# Microcontroller.net
KiCad netlist of a schematic drawn in Altium Designer
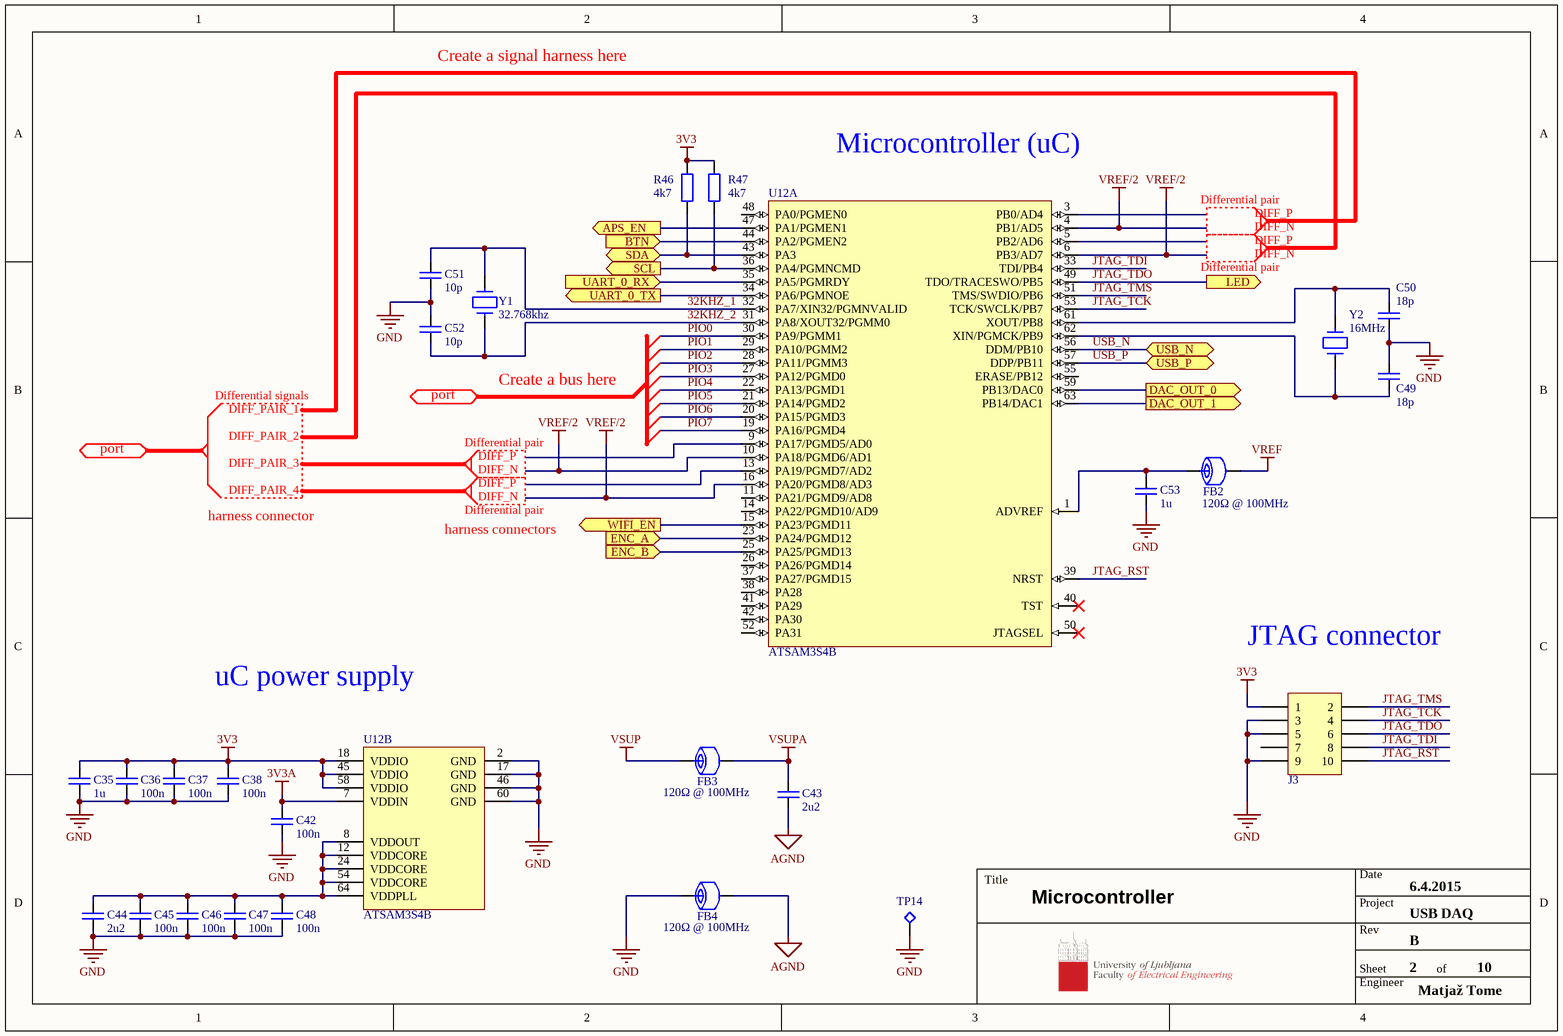
[diagram p0: Microcontroller.SchDoc]

(export (version "E")
  (design (tool "Eeschema 10.0.6"))
  (components
    (comp (ref "C35")
      (value "1u")
      (footprint "C_0603")
      (description "Generic capacitor")
      (fields (field (name "Comment") "comment"))
      (libsource (lib "DAQ") (part "Capacitor"))
    )
    (comp (ref "C36")
      (value "100n")
      (footprint "C_0603")
      (description "Generic capacitor")
      (fields (field (name "Comment") "comment"))
      (libsource (lib "DAQ") (part "Capacitor"))
    )
    (comp (ref "C37")
      (value "100n")
      (footprint "C_0603")
      (description "Generic capacitor")
      (fields (field (name "Comment") "comment"))
      (libsource (lib "DAQ") (part "Capacitor"))
    )
    (comp (ref "C38")
      (value "100n")
      (footprint "C_0603")
      (description "Generic capacitor")
      (fields (field (name "Comment") "comment"))
      (libsource (lib "DAQ") (part "Capacitor"))
    )
    (comp (ref "C42")
      (value "100n")
      (footprint "C_0603")
      (description "Generic capacitor")
      (fields (field (name "Comment") "comment"))
      (libsource (lib "DAQ") (part "Capacitor"))
    )
    (comp (ref "C43")
      (value "2u2")
      (footprint "C_0603")
      (description "Generic capacitor")
      (fields (field (name "Comment") "comment"))
      (libsource (lib "DAQ") (part "Capacitor"))
    )
    (comp (ref "C44")
      (value "2u2")
      (footprint "C_0603")
      (description "Generic capacitor")
      (fields (field (name "Comment") "comment"))
      (libsource (lib "DAQ") (part "Capacitor"))
    )
    (comp (ref "C45")
      (value "100n")
      (footprint "C_0603")
      (description "Generic capacitor")
      (fields (field (name "Comment") "comment"))
      (libsource (lib "DAQ") (part "Capacitor"))
    )
    (comp (ref "C46")
      (value "100n")
      (footprint "C_0603")
      (description "Generic capacitor")
      (fields (field (name "Comment") "comment"))
      (libsource (lib "DAQ") (part "Capacitor"))
    )
    (comp (ref "C47")
      (value "100n")
      (footprint "C_0603")
      (description "Generic capacitor")
      (fields (field (name "Comment") "comment"))
      (libsource (lib "DAQ") (part "Capacitor"))
    )
    (comp (ref "C48")
      (value "100n")
      (footprint "C_0603")
      (description "Generic capacitor")
      (fields (field (name "Comment") "comment"))
      (libsource (lib "DAQ") (part "Capacitor"))
    )
    (comp (ref "C49")
      (value "18p")
      (footprint "C_0603")
      (description "Generic capacitor")
      (fields (field (name "Comment") "comment"))
      (libsource (lib "DAQ") (part "Capacitor"))
    )
    (comp (ref "C50")
      (value "18p")
      (footprint "C_0603")
      (description "Generic capacitor")
      (fields (field (name "Comment") "comment"))
      (libsource (lib "DAQ") (part "Capacitor"))
    )
    (comp (ref "C51")
      (value "10p")
      (footprint "C_0603")
      (description "Generic capacitor")
      (fields (field (name "Comment") "comment"))
      (libsource (lib "DAQ") (part "Capacitor"))
    )
    (comp (ref "C52")
      (value "10p")
      (footprint "C_0603")
      (description "Generic capacitor")
      (fields (field (name "Comment") "comment"))
      (libsource (lib "DAQ") (part "Capacitor"))
    )
    (comp (ref "C53")
      (value "1u")
      (footprint "C_0603")
      (description "Generic capacitor")
      (fields (field (name "Comment") "comment"))
      (libsource (lib "DAQ") (part "Capacitor"))
    )
    (comp (ref "FB2")
      (value "120Ω @ 100MHz")
      (footprint "SMD_0805")
      (description "Ferrite Bead, 0805 [2012 Metric], 120 ohm, 800 mA, BLM21A Series, 0.15 ohm, ± 25%")
      (fields (field (name "MANUFACTURER") "Murata"))
      (libsource (lib "DAQ") (part "BLM21AG121SN1D"))
    )
    (comp (ref "FB3")
      (value "120Ω @ 100MHz")
      (footprint "SMD_0805")
      (description "Ferrite Bead, 0805 [2012 Metric], 120 ohm, 800 mA, BLM21A Series, 0.15 ohm, ± 25%")
      (fields (field (name "MANUFACTURER") "Murata"))
      (libsource (lib "DAQ") (part "BLM21AG121SN1D"))
    )
    (comp (ref "FB4")
      (value "120Ω @ 100MHz")
      (footprint "SMD_0805")
      (description "Ferrite Bead, 0805 [2012 Metric], 120 ohm, 800 mA, BLM21A Series, 0.15 ohm, ± 25%")
      (fields (field (name "MANUFACTURER") "Murata"))
      (libsource (lib "DAQ") (part "BLM21AG121SN1D"))
    )
    (comp (ref "J3")
      (value "M50-3600542")
      (footprint "HEADER_2X05_1.27mm")
      (description "Pin Header, Board-to-Board, 1.27 mm, 2 Rows, 10 Contacts, Surface Mount, Archer M50 Series")
      (fields (field (name "MANUFACTURER") "Harwin"))
      (libsource (lib "DAQ") (part "M50-3600542"))
    )
    (comp (ref "R46")
      (value "4k7")
      (footprint "R_0603")
      (description "Generic resistor")
      (fields (field (name "Comment") "comment"))
      (libsource (lib "DAQ") (part "Resistor"))
    )
    (comp (ref "R47")
      (value "4k7")
      (footprint "R_0603")
      (description "Generic resistor")
      (fields (field (name "Comment") "comment"))
      (libsource (lib "DAQ") (part "Resistor"))
    )
    (comp (ref "TP14")
      (value "testpoint")
      (footprint "TP1_FULL")
      (description "testpoint 1.5mm diameter no hole")
      (fields (field (name "PART NUMBER") "XXC0006"))
      (libsource (lib "DAQ") (part "Test Point"))
    )
    (comp (ref "U12")
      (value "ATSAM3S4B")
      (footprint "LQFP64")
      (description "Cortex M3 ARM microcontroller")
      (fields (field (name "PART NUMBER") "XAM0003") (field (name "MANUFACTURER") "Atmel"))
      (libsource (lib "DAQ") (part "ATSAM3SXB"))
    )
    (comp (ref "Y1")
      (value "32.768khz")
      (footprint "2X6_FLAT")
      (description "Crystal, 32.768 kHz, Cylinder Radial, 6.2mm x 2mm Dia, 12.5 pF, 20 ppm, R26 Series")
      (fields (field (name "PART NUMBER") "XCR0010") (field (name "MANUFACTURER") "RALTRON"))
      (libsource (lib "DAQ") (part "R26-32.768- 12.5"))
    )
    (comp (ref "Y2")
      (value "16MHz")
      (footprint "5X3.2")
      (description "Crystal, 16 MHz, SMD, 5mm x 3.2mm, 30 ppm, 18 pF, 30 ppm, 7A Series")
      (fields (field (name "MANUFACTURER") "TCX"))
      (libsource (lib "DAQ") (part "7A-16.000MAAJ-T"))
    )
  )
  (nets
    (net (code "1") (name "/32KHZ_1") (class "Default")
      (node (ref "C51") (pin "1") (pinfunction "1_1") (pintype "passive"))
      (node (ref "U12") (pin "32") (pinfunction "PA7/XIN32/PGMNVALID_32") (pintype "bidirectional"))
      (node (ref "Y1") (pin "2") (pinfunction "2_2") (pintype "passive"))
    )
    (net (code "2") (name "/32KHZ_2") (class "Default")
      (node (ref "C52") (pin "1") (pinfunction "1_1") (pintype "passive"))
      (node (ref "U12") (pin "31") (pinfunction "PA8/XOUT32/PGMM0_31") (pintype "bidirectional"))
      (node (ref "Y1") (pin "1") (pinfunction "1_1") (pintype "passive"))
    )
    (net (code "3") (name "/APS_EN") (class "Default")
      (node (ref "U12") (pin "47") (pinfunction "PA1/PGMEN1_47") (pintype "bidirectional"))
    )
    (net (code "4") (name "/BTN") (class "Default")
      (node (ref "U12") (pin "44") (pinfunction "PA2/PGMEN2_44") (pintype "bidirectional"))
    )
    (net (code "5") (name "/DAC_OUT_0") (class "Default")
      (node (ref "U12") (pin "59") (pinfunction "PB13/DAC0_59") (pintype "bidirectional"))
    )
    (net (code "6") (name "/DAC_OUT_1") (class "Default")
      (node (ref "U12") (pin "63") (pinfunction "PB14/DAC1_63") (pintype "bidirectional"))
    )
    (net (code "7") (name "/ENC_A") (class "Default")
      (node (ref "U12") (pin "23") (pinfunction "PA24/PGMD12_23") (pintype "bidirectional"))
    )
    (net (code "8") (name "/ENC_B") (class "Default")
      (node (ref "U12") (pin "25") (pinfunction "PA25/PGMD13_25") (pintype "bidirectional"))
    )
    (net (code "9") (name "/JTAG_RST") (class "Default")
      (node (ref "J3") (pin "10") (pinfunction "10_10") (pintype "passive"))
      (node (ref "U12") (pin "39") (pinfunction "NRST_39") (pintype "bidirectional"))
    )
    (net (code "10") (name "/JTAG_TCK") (class "Default")
      (node (ref "J3") (pin "4") (pinfunction "4_4") (pintype "passive"))
      (node (ref "U12") (pin "53") (pinfunction "TCK/SWCLK/PB7_53") (pintype "bidirectional"))
    )
    (net (code "11") (name "/JTAG_TDI") (class "Default")
      (node (ref "J3") (pin "8") (pinfunction "8_8") (pintype "passive"))
      (node (ref "U12") (pin "33") (pinfunction "TDI/PB4_33") (pintype "bidirectional"))
    )
    (net (code "12") (name "/JTAG_TDO") (class "Default")
      (node (ref "J3") (pin "6") (pinfunction "6_6") (pintype "passive"))
      (node (ref "U12") (pin "49") (pinfunction "TDO/TRACESWO/PB5_49") (pintype "bidirectional"))
    )
    (net (code "13") (name "/JTAG_TMS") (class "Default")
      (node (ref "J3") (pin "2") (pinfunction "2_2") (pintype "passive"))
      (node (ref "U12") (pin "51") (pinfunction "TMS/SWDIO/PB6_51") (pintype "bidirectional"))
    )
    (net (code "14") (name "/PIO0") (class "Default")
      (node (ref "U12") (pin "30") (pinfunction "PA9/PGMM1_30") (pintype "bidirectional"))
    )
    (net (code "15") (name "/PIO1") (class "Default")
      (node (ref "U12") (pin "29") (pinfunction "PA10/PGMM2_29") (pintype "bidirectional"))
    )
    (net (code "16") (name "/PIO2") (class "Default")
      (node (ref "U12") (pin "28") (pinfunction "PA11/PGMM3_28") (pintype "bidirectional"))
    )
    (net (code "17") (name "/PIO3") (class "Default")
      (node (ref "U12") (pin "27") (pinfunction "PA12/PGMD0_27") (pintype "bidirectional"))
    )
    (net (code "18") (name "/PIO4") (class "Default")
      (node (ref "U12") (pin "22") (pinfunction "PA13/PGMD1_22") (pintype "bidirectional"))
    )
    (net (code "19") (name "/PIO5") (class "Default")
      (node (ref "U12") (pin "21") (pinfunction "PA14/PGMD2_21") (pintype "bidirectional"))
    )
    (net (code "20") (name "/PIO6") (class "Default")
      (node (ref "U12") (pin "20") (pinfunction "PA15/PGMD3_20") (pintype "bidirectional"))
    )
    (net (code "21") (name "/PIO7") (class "Default")
      (node (ref "U12") (pin "19") (pinfunction "PA16/PGMD4_19") (pintype "bidirectional"))
    )
    (net (code "22") (name "/SCL") (class "Default")
      (node (ref "R47") (pin "1") (pintype "passive"))
      (node (ref "U12") (pin "36") (pinfunction "PA4/PGMNCMD_36") (pintype "bidirectional"))
    )
    (net (code "23") (name "/SDA") (class "Default")
      (node (ref "R46") (pin "1") (pintype "passive"))
      (node (ref "U12") (pin "43") (pinfunction "PA3_43") (pintype "bidirectional"))
    )
    (net (code "24") (name "/UART_0_RX") (class "Default")
      (node (ref "U12") (pin "35") (pinfunction "PA5/PGMRDY_35") (pintype "bidirectional"))
    )
    (net (code "25") (name "/UART_0_TX") (class "Default")
      (node (ref "U12") (pin "34") (pinfunction "PA6/PGMNOE_34") (pintype "bidirectional"))
    )
    (net (code "26") (name "/USB_N") (class "Default")
      (node (ref "U12") (pin "56") (pinfunction "DDM/PB10_56") (pintype "bidirectional"))
    )
    (net (code "27") (name "/USB_P") (class "Default")
      (node (ref "U12") (pin "57") (pinfunction "DDP/PB11_57") (pintype "bidirectional"))
    )
    (net (code "28") (name "/WIFI_EN") (class "Default")
      (node (ref "U12") (pin "15") (pinfunction "PA23/PGMD11_15") (pintype "bidirectional"))
    )
    (net (code "29") (name "3V3") (class "Default")
      (node (ref "C35") (pin "1") (pinfunction "1_1") (pintype "passive"))
      (node (ref "C36") (pin "1") (pinfunction "1_1") (pintype "passive"))
      (node (ref "C37") (pin "1") (pinfunction "1_1") (pintype "passive"))
      (node (ref "C38") (pin "1") (pinfunction "1_1") (pintype "passive"))
      (node (ref "J3") (pin "1") (pinfunction "1_1") (pintype "passive"))
      (node (ref "R46") (pin "2") (pintype "passive"))
      (node (ref "R47") (pin "2") (pintype "passive"))
      (node (ref "U12") (pin "18") (pinfunction "VDDIO_18") (pintype "power_in"))
      (node (ref "U12") (pin "45") (pinfunction "VDDIO_45") (pintype "power_in"))
      (node (ref "U12") (pin "58") (pinfunction "VDDIO_58") (pintype "power_in"))
    )
    (net (code "30") (name "3V3A") (class "Default")
      (node (ref "C42") (pin "1") (pinfunction "1_1") (pintype "passive"))
      (node (ref "U12") (pin "7") (pinfunction "VDDIN_7") (pintype "power_in"))
    )
    (net (code "31") (name "AGND") (class "Default")
      (node (ref "C43") (pin "2") (pinfunction "2_2") (pintype "passive"))
      (node (ref "FB4") (pin "2") (pintype "passive"))
    )
    (net (code "32") (name "GND") (class "Default")
      (node (ref "C35") (pin "2") (pinfunction "2_2") (pintype "passive"))
      (node (ref "C36") (pin "2") (pinfunction "2_2") (pintype "passive"))
      (node (ref "C37") (pin "2") (pinfunction "2_2") (pintype "passive"))
      (node (ref "C38") (pin "2") (pinfunction "2_2") (pintype "passive"))
      (node (ref "C42") (pin "2") (pinfunction "2_2") (pintype "passive"))
      (node (ref "C44") (pin "2") (pinfunction "2_2") (pintype "passive"))
      (node (ref "C45") (pin "2") (pinfunction "2_2") (pintype "passive"))
      (node (ref "C46") (pin "2") (pinfunction "2_2") (pintype "passive"))
      (node (ref "C47") (pin "2") (pinfunction "2_2") (pintype "passive"))
      (node (ref "C48") (pin "2") (pinfunction "2_2") (pintype "passive"))
      (node (ref "C49") (pin "2") (pinfunction "2_2") (pintype "passive"))
      (node (ref "C50") (pin "2") (pinfunction "2_2") (pintype "passive"))
      (node (ref "C51") (pin "2") (pinfunction "2_2") (pintype "passive"))
      (node (ref "C52") (pin "2") (pinfunction "2_2") (pintype "passive"))
      (node (ref "C53") (pin "2") (pinfunction "2_2") (pintype "passive"))
      (node (ref "FB4") (pin "1") (pintype "passive"))
      (node (ref "J3") (pin "3") (pinfunction "3_3") (pintype "passive"))
      (node (ref "J3") (pin "5") (pinfunction "5_5") (pintype "passive"))
      (node (ref "J3") (pin "9") (pinfunction "9_9") (pintype "passive"))
      (node (ref "TP14") (pin "1") (pinfunction "1_1") (pintype "passive"))
      (node (ref "U12") (pin "17") (pinfunction "GND_17") (pintype "power_in"))
      (node (ref "U12") (pin "2") (pinfunction "GND_2") (pintype "power_in"))
      (node (ref "U12") (pin "46") (pinfunction "GND_46") (pintype "power_in"))
      (node (ref "U12") (pin "60") (pinfunction "GND_60") (pintype "power_in"))
    )
    (net (code "33") (name "Net-(U12A-ADVREF)") (class "Default")
      (node (ref "C53") (pin "1") (pinfunction "1_1") (pintype "passive"))
      (node (ref "FB2") (pin "1") (pintype "passive"))
      (node (ref "U12") (pin "1") (pinfunction "ADVREF_1") (pintype "input"))
    )
    (net (code "34") (name "Net-(U12A-XIN{slash}PGMCK{slash}PB9)") (class "Default")
      (node (ref "C49") (pin "1") (pinfunction "1_1") (pintype "passive"))
      (node (ref "U12") (pin "62") (pinfunction "XIN/PGMCK/PB9_62") (pintype "bidirectional"))
      (node (ref "Y2") (pin "1") (pinfunction "1_1") (pintype "passive"))
    )
    (net (code "35") (name "Net-(U12A-XOUT{slash}PB8)") (class "Default")
      (node (ref "C50") (pin "1") (pinfunction "1_1") (pintype "passive"))
      (node (ref "U12") (pin "61") (pinfunction "XOUT/PB8_61") (pintype "bidirectional"))
      (node (ref "Y2") (pin "2") (pinfunction "2_2") (pintype "passive"))
    )
    (net (code "36") (name "Net-(U12B-VDDOUT)") (class "Default")
      (node (ref "C44") (pin "1") (pinfunction "1_1") (pintype "passive"))
      (node (ref "C45") (pin "1") (pinfunction "1_1") (pintype "passive"))
      (node (ref "C46") (pin "1") (pinfunction "1_1") (pintype "passive"))
      (node (ref "C47") (pin "1") (pinfunction "1_1") (pintype "passive"))
      (node (ref "C48") (pin "1") (pinfunction "1_1") (pintype "passive"))
      (node (ref "U12") (pin "12") (pinfunction "VDDCORE_12") (pintype "power_in"))
      (node (ref "U12") (pin "24") (pinfunction "VDDCORE_24") (pintype "power_in"))
      (node (ref "U12") (pin "54") (pinfunction "VDDCORE_54") (pintype "power_in"))
      (node (ref "U12") (pin "64") (pinfunction "VDDPLL_64") (pintype "power_in"))
      (node (ref "U12") (pin "8") (pinfunction "VDDOUT_8") (pintype "power_in"))
    )
    (net (code "37") (name "VREF") (class "Default") (node (ref "FB2") (pin "2") (pintype "passive")))
    (net (code "38") (name "VREF{slash}2") (class "Default")
      (node (ref "U12") (pin "10") (pinfunction "PA18/PGMD6/AD1_10") (pintype "bidirectional"))
      (node (ref "U12") (pin "16") (pinfunction "PA20/PGMD8/AD3_16") (pintype "bidirectional"))
      (node (ref "U12") (pin "4") (pinfunction "PB1/AD5_4") (pintype "bidirectional"))
      (node (ref "U12") (pin "6") (pinfunction "PB3/AD7_6") (pintype "bidirectional"))
    )
    (net (code "39") (name "VSUP") (class "Default") (node (ref "FB3") (pin "1") (pintype "passive")))
    (net (code "40") (name "VSUPA") (class "Default")
      (node (ref "C43") (pin "1") (pinfunction "1_1") (pintype "passive"))
      (node (ref "FB3") (pin "2") (pintype "passive"))
    )
    (net (code "41") (name "unconnected-(J3-Pad7)") (class "Default")
      (node (ref "J3") (pin "7") (pinfunction "7_7") (pintype "passive"))
    )
    (net (code "42") (name "unconnected-(U12A-ERASE{slash}PB12-Pad55)") (class "Default")
      (node (ref "U12") (pin "55") (pinfunction "ERASE/PB12_55") (pintype "bidirectional"))
    )
    (net (code "43") (name "unconnected-(U12A-JTAGSEL-Pad50)") (class "Default")
      (node (ref "U12") (pin "50") (pinfunction "JTAGSEL_50") (pintype "input+no_connect"))
    )
    (net (code "44") (name "unconnected-(U12A-PA0{slash}PGMEN0-Pad48)") (class "Default")
      (node (ref "U12") (pin "48") (pinfunction "PA0/PGMEN0_48") (pintype "bidirectional"))
    )
    (net (code "45") (name "unconnected-(U12A-PA17{slash}PGMD5{slash}AD0-Pad9)") (class "Default")
      (node (ref "U12") (pin "9") (pinfunction "PA17/PGMD5/AD0_9") (pintype "bidirectional"))
    )
    (net (code "46") (name "unconnected-(U12A-PA19{slash}PGMD7{slash}AD2-Pad13)") (class "Default")
      (node (ref "U12") (pin "13") (pinfunction "PA19/PGMD7/AD2_13") (pintype "bidirectional"))
    )
    (net (code "47") (name "unconnected-(U12A-PA21{slash}PGMD9{slash}AD8-Pad11)") (class "Default")
      (node (ref "U12") (pin "11") (pinfunction "PA21/PGMD9/AD8_11") (pintype "bidirectional"))
    )
    (net (code "48") (name "unconnected-(U12A-PA22{slash}PGMD10{slash}AD9-Pad14)") (class "Default")
      (node (ref "U12") (pin "14") (pinfunction "PA22/PGMD10/AD9_14") (pintype "bidirectional"))
    )
    (net (code "49") (name "unconnected-(U12A-PA26{slash}PGMD14-Pad26)") (class "Default")
      (node (ref "U12") (pin "26") (pinfunction "PA26/PGMD14_26") (pintype "bidirectional"))
    )
    (net (code "50") (name "unconnected-(U12A-PA27{slash}PGMD15-Pad37)") (class "Default")
      (node (ref "U12") (pin "37") (pinfunction "PA27/PGMD15_37") (pintype "bidirectional"))
    )
    (net (code "51") (name "unconnected-(U12A-PA28-Pad38)") (class "Default")
      (node (ref "U12") (pin "38") (pinfunction "PA28_38") (pintype "bidirectional"))
    )
    (net (code "52") (name "unconnected-(U12A-PA29-Pad41)") (class "Default")
      (node (ref "U12") (pin "41") (pinfunction "PA29_41") (pintype "bidirectional"))
    )
    (net (code "53") (name "unconnected-(U12A-PA30-Pad42)") (class "Default")
      (node (ref "U12") (pin "42") (pinfunction "PA30_42") (pintype "bidirectional"))
    )
    (net (code "54") (name "unconnected-(U12A-PA31-Pad52)") (class "Default")
      (node (ref "U12") (pin "52") (pinfunction "PA31_52") (pintype "bidirectional"))
    )
    (net (code "55") (name "unconnected-(U12A-PB0{slash}AD4-Pad3)") (class "Default")
      (node (ref "U12") (pin "3") (pinfunction "PB0/AD4_3") (pintype "bidirectional"))
    )
    (net (code "56") (name "unconnected-(U12A-PB2{slash}AD6-Pad5)") (class "Default")
      (node (ref "U12") (pin "5") (pinfunction "PB2/AD6_5") (pintype "bidirectional"))
    )
    (net (code "57") (name "unconnected-(U12A-TST-Pad40)") (class "Default")
      (node (ref "U12") (pin "40") (pinfunction "TST_40") (pintype "input+no_connect"))
    )
  )
)
